# edu_shield.net
KiCad netlist of a schematic drawn in EAGLE
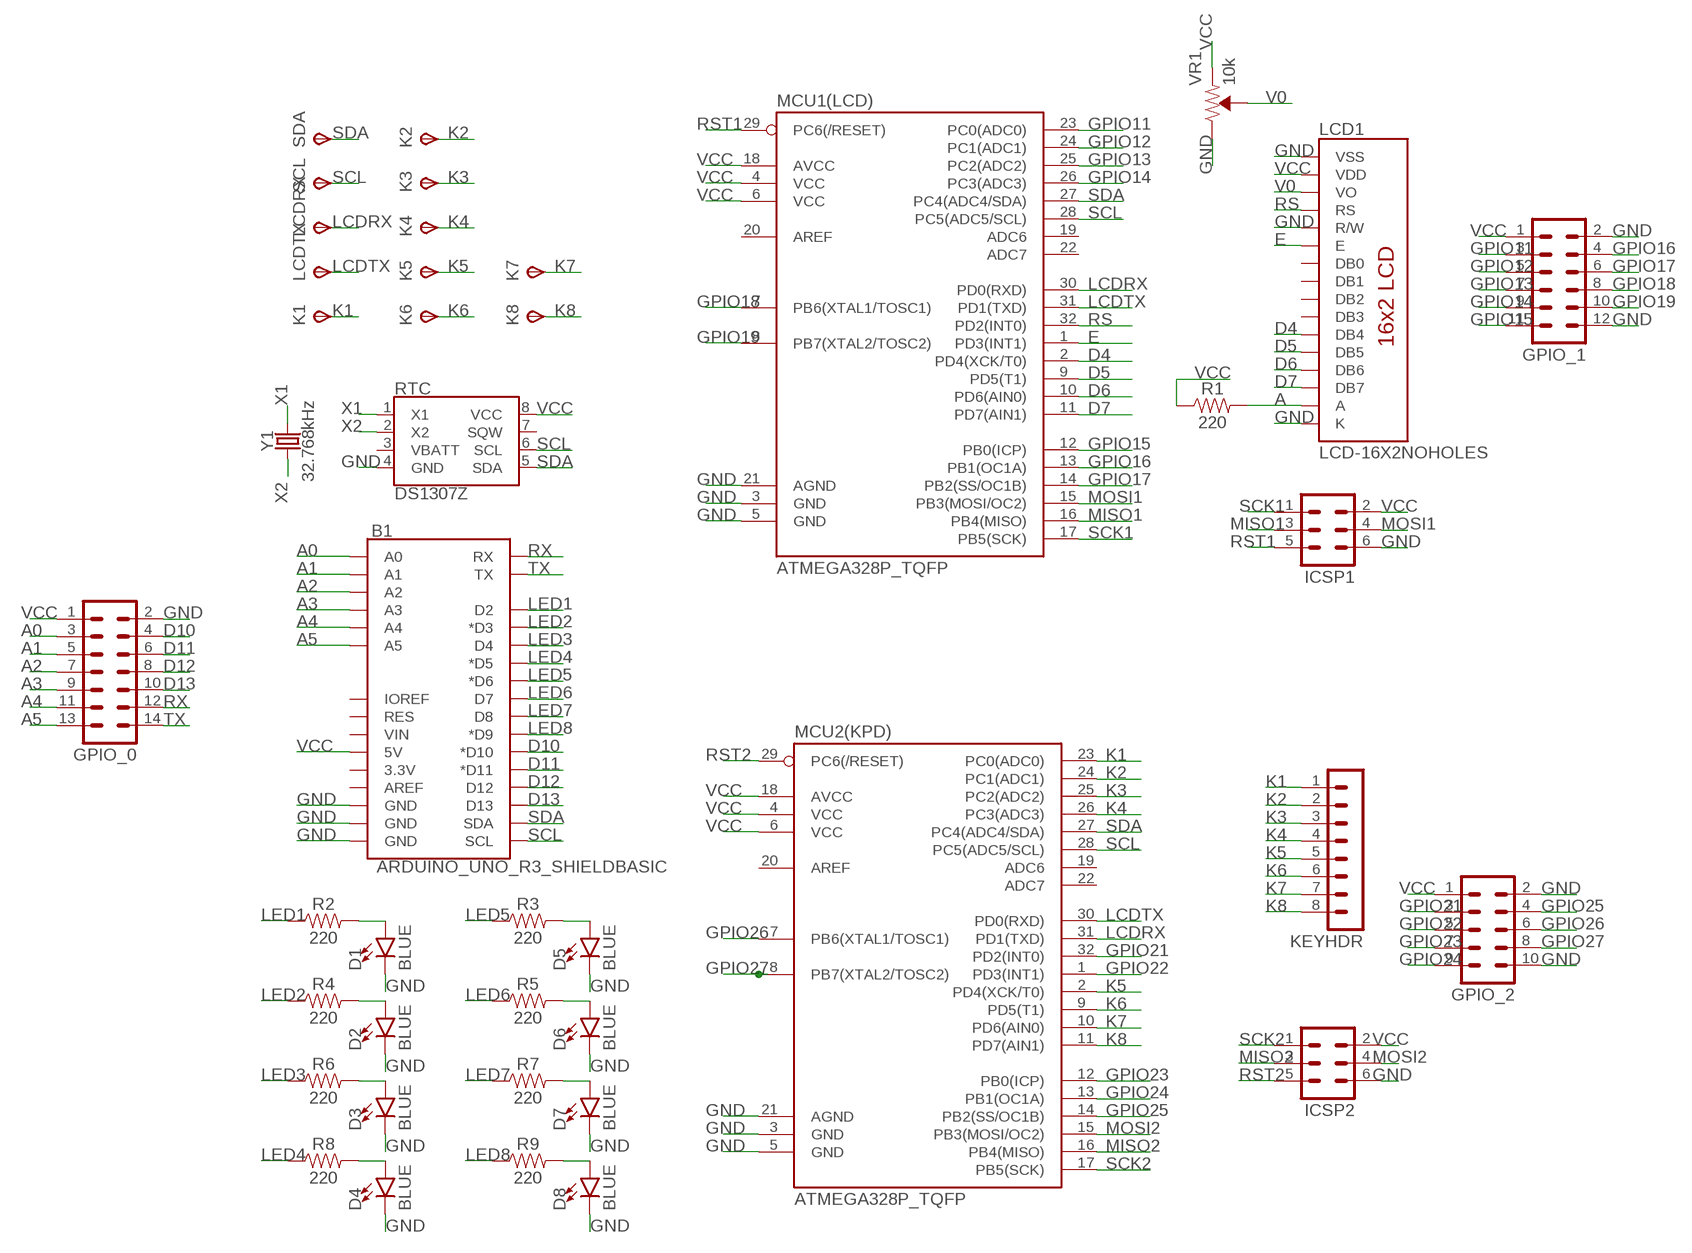
[diagram p0: schematic, sheet 1]

(export (version "E")
  (design (tool "Eeschema 10.0.6"))
  (components
    (comp (ref "B1")
      (value "ARDUINO_UNO_R3_SHIELDBASIC")
      (footprint "eagle-import:UNO_R3_SHIELD")
      (libsource (lib "eagle-import") (part "ARDUINO_UNO_R3_SHIELDBASIC"))
    )
    (comp (ref "D1")
      (value "BLUE")
      (footprint "eagle-import:LED-0603")
      (fields (field (name "MPN") "KPHD-1608LVVBC-D"))
      (libsource (lib "eagle-import") (part "LED-BLUE0603"))
    )
    (comp (ref "D2")
      (value "BLUE")
      (footprint "eagle-import:LED-0603")
      (fields (field (name "MPN") "KPHD-1608LVVBC-D"))
      (libsource (lib "eagle-import") (part "LED-BLUE0603"))
    )
    (comp (ref "D3")
      (value "BLUE")
      (footprint "eagle-import:LED-0603")
      (fields (field (name "MPN") "KPHD-1608LVVBC-D"))
      (libsource (lib "eagle-import") (part "LED-BLUE0603"))
    )
    (comp (ref "D4")
      (value "BLUE")
      (footprint "eagle-import:LED-0603")
      (fields (field (name "MPN") "KPHD-1608LVVBC-D"))
      (libsource (lib "eagle-import") (part "LED-BLUE0603"))
    )
    (comp (ref "D5")
      (value "BLUE")
      (footprint "eagle-import:LED-0603")
      (fields (field (name "MPN") "KPHD-1608LVVBC-D"))
      (libsource (lib "eagle-import") (part "LED-BLUE0603"))
    )
    (comp (ref "D6")
      (value "BLUE")
      (footprint "eagle-import:LED-0603")
      (fields (field (name "MPN") "KPHD-1608LVVBC-D"))
      (libsource (lib "eagle-import") (part "LED-BLUE0603"))
    )
    (comp (ref "D7")
      (value "BLUE")
      (footprint "eagle-import:LED-0603")
      (fields (field (name "MPN") "KPHD-1608LVVBC-D"))
      (libsource (lib "eagle-import") (part "LED-BLUE0603"))
    )
    (comp (ref "D8")
      (value "BLUE")
      (footprint "eagle-import:LED-0603")
      (fields (field (name "MPN") "KPHD-1608LVVBC-D"))
      (libsource (lib "eagle-import") (part "LED-BLUE0603"))
    )
    (comp (ref "GPIO_0")
      (value "MA07-2")
      (footprint "eagle-import:MA07-2")
      (libsource (lib "eagle-import") (part "MA07-2"))
    )
    (comp (ref "GPIO_1")
      (value "MA06-2")
      (footprint "eagle-import:MA06-2")
      (libsource (lib "eagle-import") (part "MA06-2"))
    )
    (comp (ref "GPIO_2")
      (value "MA05-2")
      (footprint "eagle-import:MA05-2")
      (libsource (lib "eagle-import") (part "MA05-2"))
    )
    (comp (ref "ICSP1")
      (value "MA03-2")
      (footprint "eagle-import:MA03-2")
      (libsource (lib "eagle-import") (part "MA03-2"))
    )
    (comp (ref "ICSP2")
      (value "MA03-2")
      (footprint "eagle-import:MA03-2")
      (libsource (lib "eagle-import") (part "MA03-2"))
    )
    (comp (ref "K1")
      (value "TPSTP06SQ")
      (footprint "eagle-import:TP06SQ")
      (libsource (lib "eagle-import") (part "TPSTP06SQ"))
    )
    (comp (ref "K2")
      (value "TPSTP06SQ")
      (footprint "eagle-import:TP06SQ")
      (libsource (lib "eagle-import") (part "TPSTP06SQ"))
    )
    (comp (ref "K3")
      (value "TPSTP06SQ")
      (footprint "eagle-import:TP06SQ")
      (libsource (lib "eagle-import") (part "TPSTP06SQ"))
    )
    (comp (ref "K4")
      (value "TPSTP06SQ")
      (footprint "eagle-import:TP06SQ")
      (libsource (lib "eagle-import") (part "TPSTP06SQ"))
    )
    (comp (ref "K5")
      (value "TPSTP06SQ")
      (footprint "eagle-import:TP06SQ")
      (libsource (lib "eagle-import") (part "TPSTP06SQ"))
    )
    (comp (ref "K6")
      (value "TPSTP06SQ")
      (footprint "eagle-import:TP06SQ")
      (libsource (lib "eagle-import") (part "TPSTP06SQ"))
    )
    (comp (ref "K7")
      (value "TPSTP06SQ")
      (footprint "eagle-import:TP06SQ")
      (libsource (lib "eagle-import") (part "TPSTP06SQ"))
    )
    (comp (ref "K8")
      (value "TPSTP06SQ")
      (footprint "eagle-import:TP06SQ")
      (libsource (lib "eagle-import") (part "TPSTP06SQ"))
    )
    (comp (ref "KEYHDR")
      (value "MA08-1")
      (footprint "eagle-import:MA08-1")
      (libsource (lib "eagle-import") (part "MA08-1"))
    )
    (comp (ref "LCD1")
      (value "LCD-16X2NOHOLES")
      (footprint "eagle-import:LCD-16X2_NOHOLESNOSILK")
      (libsource (lib "eagle-import") (part "LCD-16X2NOHOLES"))
    )
    (comp (ref "LCDRX")
      (value "TPSTP06SQ")
      (footprint "eagle-import:TP06SQ")
      (libsource (lib "eagle-import") (part "TPSTP06SQ"))
    )
    (comp (ref "LCDTX")
      (value "TPSTP06SQ")
      (footprint "eagle-import:TP06SQ")
      (libsource (lib "eagle-import") (part "TPSTP06SQ"))
    )
    (comp (ref "MCU1(LCD)")
      (value "ATMEGA328P_TQFP")
      (footprint "eagle-import:TQFP32-08")
      (libsource (lib "eagle-import") (part "ATMEGA328P_TQFP"))
    )
    (comp (ref "MCU2(KPD)")
      (value "ATMEGA328P_TQFP")
      (footprint "eagle-import:TQFP32-08")
      (libsource (lib "eagle-import") (part "ATMEGA328P_TQFP"))
    )
    (comp (ref "R1")
      (value "220")
      (footprint "eagle-import:0603")
      (fields (field (name "MPN") "MC0603SAF2200T5E"))
      (libsource (lib "eagle-import") (part "220KOHM-0603-1/10W-1%"))
    )
    (comp (ref "R2")
      (value "220")
      (footprint "eagle-import:0603")
      (fields (field (name "MPN") "MC0603SAF2200T5E"))
      (libsource (lib "eagle-import") (part "220KOHM-0603-1/10W-1%"))
    )
    (comp (ref "R3")
      (value "220")
      (footprint "eagle-import:0603")
      (fields (field (name "MPN") "MC0603SAF2200T5E"))
      (libsource (lib "eagle-import") (part "220KOHM-0603-1/10W-1%"))
    )
    (comp (ref "R4")
      (value "220")
      (footprint "eagle-import:0603")
      (fields (field (name "MPN") "MC0603SAF2200T5E"))
      (libsource (lib "eagle-import") (part "220KOHM-0603-1/10W-1%"))
    )
    (comp (ref "R5")
      (value "220")
      (footprint "eagle-import:0603")
      (fields (field (name "MPN") "MC0603SAF2200T5E"))
      (libsource (lib "eagle-import") (part "220KOHM-0603-1/10W-1%"))
    )
    (comp (ref "R6")
      (value "220")
      (footprint "eagle-import:0603")
      (fields (field (name "MPN") "MC0603SAF2200T5E"))
      (libsource (lib "eagle-import") (part "220KOHM-0603-1/10W-1%"))
    )
    (comp (ref "R7")
      (value "220")
      (footprint "eagle-import:0603")
      (fields (field (name "MPN") "MC0603SAF2200T5E"))
      (libsource (lib "eagle-import") (part "220KOHM-0603-1/10W-1%"))
    )
    (comp (ref "R8")
      (value "220")
      (footprint "eagle-import:0603")
      (fields (field (name "MPN") "MC0603SAF2200T5E"))
      (libsource (lib "eagle-import") (part "220KOHM-0603-1/10W-1%"))
    )
    (comp (ref "R9")
      (value "220")
      (footprint "eagle-import:0603")
      (fields (field (name "MPN") "MC0603SAF2200T5E"))
      (libsource (lib "eagle-import") (part "220KOHM-0603-1/10W-1%"))
    )
    (comp (ref "RTC")
      (value "DS1307Z")
      (footprint "eagle-import:SO08-0.15")
      (fields (field (name "MPN") "DS1307Z+T&R"))
      (libsource (lib "eagle-import") (part "DS1307Z"))
    )
    (comp (ref "SCL")
      (value "TPSTP06SQ")
      (footprint "eagle-import:TP06SQ")
      (libsource (lib "eagle-import") (part "TPSTP06SQ"))
    )
    (comp (ref "SDA")
      (value "TPSTP06SQ")
      (footprint "eagle-import:TP06SQ")
      (libsource (lib "eagle-import") (part "TPSTP06SQ"))
    )
    (comp (ref "VR1")
      (value "10k")
      (footprint "eagle-import:TRIMPOT-PTH-3386U")
      (fields (field (name "MF") "BOURNS, INC.") (field (name "MPN") "3296W-1-103LF"))
      (libsource (lib "eagle-import") (part "TRIMPOT-PTH-10MM-KNOB-1/2W-10%"))
    )
    (comp (ref "Y1")
      (value "32.768kHz")
      (footprint "eagle-import:CRYSTAL-PTH-2X6-CYL")
      (fields (field (name "MF") "Abracon Corporation") (field (name "MPN") "AB38T-32.768KHZ"))
      (libsource (lib "eagle-import") (part "CRYSTAL-32.768KHZPTH-2X6"))
    )
  )
  (nets
    (net (code "1") (name "/A") (class "Default")
      (node (ref "LCD1") (pin "15") (pinfunction "A_15") (pintype "power_in"))
      (node (ref "R1") (pin "2") (pinfunction "2_2") (pintype "passive"))
    )
    (net (code "2") (name "/A0") (class "Default")
      (node (ref "B1") (pin "A0") (pinfunction "A0_A0") (pintype "bidirectional"))
      (node (ref "GPIO_0") (pin "3") (pinfunction "3_3") (pintype "passive"))
    )
    (net (code "3") (name "/A1") (class "Default")
      (node (ref "B1") (pin "A1") (pinfunction "A1_A1") (pintype "bidirectional"))
      (node (ref "GPIO_0") (pin "5") (pinfunction "5_5") (pintype "passive"))
    )
    (net (code "4") (name "/A2") (class "Default")
      (node (ref "B1") (pin "A2") (pinfunction "A2_A2") (pintype "bidirectional"))
      (node (ref "GPIO_0") (pin "7") (pinfunction "7_7") (pintype "passive"))
    )
    (net (code "5") (name "/A3") (class "Default")
      (node (ref "B1") (pin "A3") (pinfunction "A3_A3") (pintype "bidirectional"))
      (node (ref "GPIO_0") (pin "9") (pinfunction "9_9") (pintype "passive"))
    )
    (net (code "6") (name "/A4") (class "Default")
      (node (ref "B1") (pin "A4") (pinfunction "A4_A4") (pintype "bidirectional"))
      (node (ref "GPIO_0") (pin "11") (pinfunction "11_11") (pintype "passive"))
    )
    (net (code "7") (name "/A5") (class "Default")
      (node (ref "B1") (pin "A5") (pinfunction "A5_A5") (pintype "bidirectional"))
      (node (ref "GPIO_0") (pin "13") (pinfunction "13_13") (pintype "passive"))
    )
    (net (code "8") (name "/D4") (class "Default")
      (node (ref "LCD1") (pin "11") (pinfunction "DB4_11") (pintype "bidirectional"))
      (node (ref "MCU1(LCD)") (pin "2") (pinfunction "PD4(XCK/T0)_2") (pintype "bidirectional"))
    )
    (net (code "9") (name "/D5") (class "Default")
      (node (ref "LCD1") (pin "12") (pinfunction "DB5_12") (pintype "bidirectional"))
      (node (ref "MCU1(LCD)") (pin "9") (pinfunction "PD5(T1)_9") (pintype "bidirectional"))
    )
    (net (code "10") (name "/D6") (class "Default")
      (node (ref "LCD1") (pin "13") (pinfunction "DB6_13") (pintype "bidirectional"))
      (node (ref "MCU1(LCD)") (pin "10") (pinfunction "PD6(AIN0)_10") (pintype "bidirectional"))
    )
    (net (code "11") (name "/D7") (class "Default")
      (node (ref "LCD1") (pin "14") (pinfunction "DB7_14") (pintype "bidirectional"))
      (node (ref "MCU1(LCD)") (pin "11") (pinfunction "PD7(AIN1)_11") (pintype "bidirectional"))
    )
    (net (code "12") (name "/D10") (class "Default")
      (node (ref "B1") (pin "D10") (pinfunction "*D10_D10") (pintype "bidirectional"))
      (node (ref "GPIO_0") (pin "4") (pinfunction "4_4") (pintype "passive"))
    )
    (net (code "13") (name "/D11") (class "Default")
      (node (ref "B1") (pin "D11") (pinfunction "*D11_D11") (pintype "bidirectional"))
      (node (ref "GPIO_0") (pin "6") (pinfunction "6_6") (pintype "passive"))
    )
    (net (code "14") (name "/D12") (class "Default")
      (node (ref "B1") (pin "D12") (pinfunction "D12_D12") (pintype "bidirectional"))
      (node (ref "GPIO_0") (pin "8") (pinfunction "8_8") (pintype "passive"))
    )
    (net (code "15") (name "/D13") (class "Default")
      (node (ref "B1") (pin "D13") (pinfunction "D13_D13") (pintype "bidirectional"))
      (node (ref "GPIO_0") (pin "10") (pinfunction "10_10") (pintype "passive"))
    )
    (net (code "16") (name "/E") (class "Default")
      (node (ref "LCD1") (pin "6") (pinfunction "E_6") (pintype "input"))
      (node (ref "MCU1(LCD)") (pin "1") (pinfunction "PD3(INT1)_1") (pintype "bidirectional"))
    )
    (net (code "17") (name "/GND") (class "Default")
      (node (ref "B1") (pin "GND@0") (pinfunction "GND_GND@0") (pintype "bidirectional"))
      (node (ref "B1") (pin "GND@1") (pinfunction "GND_GND@1") (pintype "bidirectional"))
      (node (ref "B1") (pin "GND@2") (pinfunction "GND_GND@2") (pintype "bidirectional"))
      (node (ref "D1") (pin "C") (pinfunction "C_C") (pintype "passive"))
      (node (ref "D2") (pin "C") (pinfunction "C_C") (pintype "passive"))
      (node (ref "D3") (pin "C") (pinfunction "C_C") (pintype "passive"))
      (node (ref "D4") (pin "C") (pinfunction "C_C") (pintype "passive"))
      (node (ref "D5") (pin "C") (pinfunction "C_C") (pintype "passive"))
      (node (ref "D6") (pin "C") (pinfunction "C_C") (pintype "passive"))
      (node (ref "D7") (pin "C") (pinfunction "C_C") (pintype "passive"))
      (node (ref "D8") (pin "C") (pinfunction "C_C") (pintype "passive"))
      (node (ref "GPIO_0") (pin "2") (pinfunction "2_2") (pintype "passive"))
      (node (ref "GPIO_1") (pin "12") (pinfunction "12_12") (pintype "passive"))
      (node (ref "GPIO_1") (pin "2") (pinfunction "2_2") (pintype "passive"))
      (node (ref "GPIO_2") (pin "10") (pinfunction "10_10") (pintype "passive"))
      (node (ref "GPIO_2") (pin "2") (pinfunction "2_2") (pintype "passive"))
      (node (ref "ICSP1") (pin "6") (pinfunction "6_6") (pintype "passive"))
      (node (ref "ICSP2") (pin "6") (pinfunction "6_6") (pintype "passive"))
      (node (ref "LCD1") (pin "1") (pinfunction "VSS_1") (pintype "power_in"))
      (node (ref "LCD1") (pin "16") (pinfunction "K_16") (pintype "power_in"))
      (node (ref "LCD1") (pin "5") (pinfunction "R/W_5") (pintype "input"))
      (node (ref "MCU1(LCD)") (pin "21") (pinfunction "AGND_21") (pintype "bidirectional"))
      (node (ref "MCU1(LCD)") (pin "3") (pinfunction "GND_3") (pintype "bidirectional"))
      (node (ref "MCU1(LCD)") (pin "5") (pinfunction "GND_5") (pintype "bidirectional"))
      (node (ref "MCU2(KPD)") (pin "21") (pinfunction "AGND_21") (pintype "bidirectional"))
      (node (ref "MCU2(KPD)") (pin "3") (pinfunction "GND_3") (pintype "bidirectional"))
      (node (ref "MCU2(KPD)") (pin "5") (pinfunction "GND_5") (pintype "bidirectional"))
      (node (ref "RTC") (pin "4") (pinfunction "GND_4") (pintype "bidirectional"))
      (node (ref "VR1") (pin "3") (pinfunction "CW_3") (pintype "passive"))
    )
    (net (code "18") (name "/GPIO11") (class "Default")
      (node (ref "GPIO_1") (pin "3") (pinfunction "3_3") (pintype "passive"))
      (node (ref "MCU1(LCD)") (pin "23") (pinfunction "PC0(ADC0)_23") (pintype "bidirectional"))
    )
    (net (code "19") (name "/GPIO12") (class "Default")
      (node (ref "GPIO_1") (pin "5") (pinfunction "5_5") (pintype "passive"))
      (node (ref "MCU1(LCD)") (pin "24") (pinfunction "PC1(ADC1)_24") (pintype "bidirectional"))
    )
    (net (code "20") (name "/GPIO13") (class "Default")
      (node (ref "GPIO_1") (pin "7") (pinfunction "7_7") (pintype "passive"))
      (node (ref "MCU1(LCD)") (pin "25") (pinfunction "PC2(ADC2)_25") (pintype "bidirectional"))
    )
    (net (code "21") (name "/GPIO14") (class "Default")
      (node (ref "GPIO_1") (pin "9") (pinfunction "9_9") (pintype "passive"))
      (node (ref "MCU1(LCD)") (pin "26") (pinfunction "PC3(ADC3)_26") (pintype "bidirectional"))
    )
    (net (code "22") (name "/GPIO15") (class "Default")
      (node (ref "GPIO_1") (pin "11") (pinfunction "11_11") (pintype "passive"))
      (node (ref "MCU1(LCD)") (pin "12") (pinfunction "PB0(ICP)_12") (pintype "bidirectional"))
    )
    (net (code "23") (name "/GPIO16") (class "Default")
      (node (ref "GPIO_1") (pin "4") (pinfunction "4_4") (pintype "passive"))
      (node (ref "MCU1(LCD)") (pin "13") (pinfunction "PB1(OC1A)_13") (pintype "bidirectional"))
    )
    (net (code "24") (name "/GPIO17") (class "Default")
      (node (ref "GPIO_1") (pin "6") (pinfunction "6_6") (pintype "passive"))
      (node (ref "MCU1(LCD)") (pin "14") (pinfunction "PB2(SS/OC1B)_14") (pintype "bidirectional"))
    )
    (net (code "25") (name "/GPIO18") (class "Default")
      (node (ref "GPIO_1") (pin "8") (pinfunction "8_8") (pintype "passive"))
      (node (ref "MCU1(LCD)") (pin "7") (pinfunction "PB6(XTAL1/TOSC1)_7") (pintype "bidirectional"))
    )
    (net (code "26") (name "/GPIO19") (class "Default")
      (node (ref "GPIO_1") (pin "10") (pinfunction "10_10") (pintype "passive"))
      (node (ref "MCU1(LCD)") (pin "8") (pinfunction "PB7(XTAL2/TOSC2)_8") (pintype "bidirectional"))
    )
    (net (code "27") (name "/GPIO21") (class "Default")
      (node (ref "GPIO_2") (pin "3") (pinfunction "3_3") (pintype "passive"))
      (node (ref "MCU2(KPD)") (pin "32") (pinfunction "PD2(INT0)_32") (pintype "bidirectional"))
    )
    (net (code "28") (name "/GPIO22") (class "Default")
      (node (ref "GPIO_2") (pin "5") (pinfunction "5_5") (pintype "passive"))
      (node (ref "MCU2(KPD)") (pin "1") (pinfunction "PD3(INT1)_1") (pintype "bidirectional"))
    )
    (net (code "29") (name "/GPIO23") (class "Default")
      (node (ref "GPIO_2") (pin "7") (pinfunction "7_7") (pintype "passive"))
      (node (ref "MCU2(KPD)") (pin "12") (pinfunction "PB0(ICP)_12") (pintype "bidirectional"))
    )
    (net (code "30") (name "/GPIO24") (class "Default")
      (node (ref "GPIO_2") (pin "9") (pinfunction "9_9") (pintype "passive"))
      (node (ref "MCU2(KPD)") (pin "13") (pinfunction "PB1(OC1A)_13") (pintype "bidirectional"))
    )
    (net (code "31") (name "/GPIO25") (class "Default")
      (node (ref "GPIO_2") (pin "4") (pinfunction "4_4") (pintype "passive"))
      (node (ref "MCU2(KPD)") (pin "14") (pinfunction "PB2(SS/OC1B)_14") (pintype "bidirectional"))
    )
    (net (code "32") (name "/GPIO26") (class "Default")
      (node (ref "GPIO_2") (pin "6") (pinfunction "6_6") (pintype "passive"))
      (node (ref "MCU2(KPD)") (pin "7") (pinfunction "PB6(XTAL1/TOSC1)_7") (pintype "bidirectional"))
    )
    (net (code "33") (name "/GPIO27") (class "Default")
      (node (ref "GPIO_2") (pin "8") (pinfunction "8_8") (pintype "passive"))
      (node (ref "MCU2(KPD)") (pin "8") (pinfunction "PB7(XTAL2/TOSC2)_8") (pintype "bidirectional"))
    )
    (net (code "34") (name "/K1") (class "Default")
      (node (ref "K1") (pin "TP") (pinfunction "PP_TP") (pintype "input"))
      (node (ref "KEYHDR") (pin "1") (pinfunction "1_1") (pintype "passive"))
      (node (ref "MCU2(KPD)") (pin "23") (pinfunction "PC0(ADC0)_23") (pintype "bidirectional"))
    )
    (net (code "35") (name "/K2") (class "Default")
      (node (ref "K2") (pin "TP") (pinfunction "PP_TP") (pintype "input"))
      (node (ref "KEYHDR") (pin "2") (pinfunction "2_2") (pintype "passive"))
      (node (ref "MCU2(KPD)") (pin "24") (pinfunction "PC1(ADC1)_24") (pintype "bidirectional"))
    )
    (net (code "36") (name "/K3") (class "Default")
      (node (ref "K3") (pin "TP") (pinfunction "PP_TP") (pintype "input"))
      (node (ref "KEYHDR") (pin "3") (pinfunction "3_3") (pintype "passive"))
      (node (ref "MCU2(KPD)") (pin "25") (pinfunction "PC2(ADC2)_25") (pintype "bidirectional"))
    )
    (net (code "37") (name "/K4") (class "Default")
      (node (ref "K4") (pin "TP") (pinfunction "PP_TP") (pintype "input"))
      (node (ref "KEYHDR") (pin "4") (pinfunction "4_4") (pintype "passive"))
      (node (ref "MCU2(KPD)") (pin "26") (pinfunction "PC3(ADC3)_26") (pintype "bidirectional"))
    )
    (net (code "38") (name "/K5") (class "Default")
      (node (ref "K5") (pin "TP") (pinfunction "PP_TP") (pintype "input"))
      (node (ref "KEYHDR") (pin "5") (pinfunction "5_5") (pintype "passive"))
      (node (ref "MCU2(KPD)") (pin "2") (pinfunction "PD4(XCK/T0)_2") (pintype "bidirectional"))
    )
    (net (code "39") (name "/K6") (class "Default")
      (node (ref "K6") (pin "TP") (pinfunction "PP_TP") (pintype "input"))
      (node (ref "KEYHDR") (pin "6") (pinfunction "6_6") (pintype "passive"))
      (node (ref "MCU2(KPD)") (pin "9") (pinfunction "PD5(T1)_9") (pintype "bidirectional"))
    )
    (net (code "40") (name "/K7") (class "Default")
      (node (ref "K7") (pin "TP") (pinfunction "PP_TP") (pintype "input"))
      (node (ref "KEYHDR") (pin "7") (pinfunction "7_7") (pintype "passive"))
      (node (ref "MCU2(KPD)") (pin "10") (pinfunction "PD6(AIN0)_10") (pintype "bidirectional"))
    )
    (net (code "41") (name "/K8") (class "Default")
      (node (ref "K8") (pin "TP") (pinfunction "PP_TP") (pintype "input"))
      (node (ref "KEYHDR") (pin "8") (pinfunction "8_8") (pintype "passive"))
      (node (ref "MCU2(KPD)") (pin "11") (pinfunction "PD7(AIN1)_11") (pintype "bidirectional"))
    )
    (net (code "42") (name "/LCDRX") (class "Default")
      (node (ref "LCDRX") (pin "TP") (pinfunction "PP_TP") (pintype "input"))
      (node (ref "MCU1(LCD)") (pin "30") (pinfunction "PD0(RXD)_30") (pintype "bidirectional"))
      (node (ref "MCU2(KPD)") (pin "31") (pinfunction "PD1(TXD)_31") (pintype "bidirectional"))
    )
    (net (code "43") (name "/LCDTX") (class "Default")
      (node (ref "LCDTX") (pin "TP") (pinfunction "PP_TP") (pintype "input"))
      (node (ref "MCU1(LCD)") (pin "31") (pinfunction "PD1(TXD)_31") (pintype "bidirectional"))
      (node (ref "MCU2(KPD)") (pin "30") (pinfunction "PD0(RXD)_30") (pintype "bidirectional"))
    )
    (net (code "44") (name "/LED1") (class "Default")
      (node (ref "B1") (pin "D2") (pinfunction "D2_D2") (pintype "bidirectional"))
      (node (ref "R2") (pin "1") (pinfunction "1_1") (pintype "passive"))
    )
    (net (code "45") (name "/LED2") (class "Default")
      (node (ref "B1") (pin "D3") (pinfunction "*D3_D3") (pintype "bidirectional"))
      (node (ref "R4") (pin "1") (pinfunction "1_1") (pintype "passive"))
    )
    (net (code "46") (name "/LED3") (class "Default")
      (node (ref "B1") (pin "D4") (pinfunction "D4_D4") (pintype "bidirectional"))
      (node (ref "R6") (pin "1") (pinfunction "1_1") (pintype "passive"))
    )
    (net (code "47") (name "/LED4") (class "Default")
      (node (ref "B1") (pin "D5") (pinfunction "*D5_D5") (pintype "bidirectional"))
      (node (ref "R8") (pin "1") (pinfunction "1_1") (pintype "passive"))
    )
    (net (code "48") (name "/LED5") (class "Default")
      (node (ref "B1") (pin "D6") (pinfunction "*D6_D6") (pintype "bidirectional"))
      (node (ref "R3") (pin "1") (pinfunction "1_1") (pintype "passive"))
    )
    (net (code "49") (name "/LED6") (class "Default")
      (node (ref "B1") (pin "D7") (pinfunction "D7_D7") (pintype "bidirectional"))
      (node (ref "R5") (pin "1") (pinfunction "1_1") (pintype "passive"))
    )
    (net (code "50") (name "/LED7") (class "Default")
      (node (ref "B1") (pin "D8") (pinfunction "D8_D8") (pintype "bidirectional"))
      (node (ref "R7") (pin "1") (pinfunction "1_1") (pintype "passive"))
    )
    (net (code "51") (name "/LED8") (class "Default")
      (node (ref "B1") (pin "D9") (pinfunction "*D9_D9") (pintype "bidirectional"))
      (node (ref "R9") (pin "1") (pinfunction "1_1") (pintype "passive"))
    )
    (net (code "52") (name "/MISO1") (class "Default")
      (node (ref "ICSP1") (pin "3") (pinfunction "3_3") (pintype "passive"))
      (node (ref "MCU1(LCD)") (pin "16") (pinfunction "PB4(MISO)_16") (pintype "bidirectional"))
    )
    (net (code "53") (name "/MISO2") (class "Default")
      (node (ref "ICSP2") (pin "3") (pinfunction "3_3") (pintype "passive"))
      (node (ref "MCU2(KPD)") (pin "16") (pinfunction "PB4(MISO)_16") (pintype "bidirectional"))
    )
    (net (code "54") (name "/MOSI1") (class "Default")
      (node (ref "ICSP1") (pin "4") (pinfunction "4_4") (pintype "passive"))
      (node (ref "MCU1(LCD)") (pin "15") (pinfunction "PB3(MOSI/OC2)_15") (pintype "bidirectional"))
    )
    (net (code "55") (name "/MOSI2") (class "Default")
      (node (ref "ICSP2") (pin "4") (pinfunction "4_4") (pintype "passive"))
      (node (ref "MCU2(KPD)") (pin "15") (pinfunction "PB3(MOSI/OC2)_15") (pintype "bidirectional"))
    )
    (net (code "56") (name "/RS") (class "Default")
      (node (ref "LCD1") (pin "4") (pinfunction "RS_4") (pintype "input"))
      (node (ref "MCU1(LCD)") (pin "32") (pinfunction "PD2(INT0)_32") (pintype "bidirectional"))
    )
    (net (code "57") (name "/RST1") (class "Default")
      (node (ref "ICSP1") (pin "5") (pinfunction "5_5") (pintype "passive"))
      (node (ref "MCU1(LCD)") (pin "29") (pinfunction "PC6(/RESET)_29") (pintype "bidirectional"))
    )
    (net (code "58") (name "/RST2") (class "Default")
      (node (ref "ICSP2") (pin "5") (pinfunction "5_5") (pintype "passive"))
      (node (ref "MCU2(KPD)") (pin "29") (pinfunction "PC6(/RESET)_29") (pintype "bidirectional"))
    )
    (net (code "59") (name "/RX") (class "Default")
      (node (ref "B1") (pin "RX") (pinfunction "RX_RX") (pintype "bidirectional"))
      (node (ref "GPIO_0") (pin "12") (pinfunction "12_12") (pintype "passive"))
    )
    (net (code "60") (name "/SCK1") (class "Default")
      (node (ref "ICSP1") (pin "1") (pinfunction "1_1") (pintype "passive"))
      (node (ref "MCU1(LCD)") (pin "17") (pinfunction "PB5(SCK)_17") (pintype "bidirectional"))
    )
    (net (code "61") (name "/SCK2") (class "Default")
      (node (ref "ICSP2") (pin "1") (pinfunction "1_1") (pintype "passive"))
      (node (ref "MCU2(KPD)") (pin "17") (pinfunction "PB5(SCK)_17") (pintype "bidirectional"))
    )
    (net (code "62") (name "/SCL") (class "Default")
      (node (ref "B1") (pin "SCL") (pinfunction "SCL_SCL") (pintype "bidirectional"))
      (node (ref "MCU1(LCD)") (pin "28") (pinfunction "PC5(ADC5/SCL)_28") (pintype "bidirectional"))
      (node (ref "MCU2(KPD)") (pin "28") (pinfunction "PC5(ADC5/SCL)_28") (pintype "bidirectional"))
      (node (ref "RTC") (pin "6") (pinfunction "SCL_6") (pintype "bidirectional"))
      (node (ref "SCL") (pin "TP") (pinfunction "PP_TP") (pintype "input"))
    )
    (net (code "63") (name "/SDA") (class "Default")
      (node (ref "B1") (pin "SDA") (pinfunction "SDA_SDA") (pintype "bidirectional"))
      (node (ref "MCU1(LCD)") (pin "27") (pinfunction "PC4(ADC4/SDA)_27") (pintype "bidirectional"))
      (node (ref "MCU2(KPD)") (pin "27") (pinfunction "PC4(ADC4/SDA)_27") (pintype "bidirectional"))
      (node (ref "RTC") (pin "5") (pinfunction "SDA_5") (pintype "bidirectional"))
      (node (ref "SDA") (pin "TP") (pinfunction "PP_TP") (pintype "input"))
    )
    (net (code "64") (name "/TX") (class "Default")
      (node (ref "B1") (pin "TX") (pinfunction "TX_TX") (pintype "bidirectional"))
      (node (ref "GPIO_0") (pin "14") (pinfunction "14_14") (pintype "passive"))
    )
    (net (code "65") (name "/V0") (class "Default")
      (node (ref "LCD1") (pin "3") (pinfunction "VO_3") (pintype "bidirectional"))
      (node (ref "VR1") (pin "2") (pinfunction "WIPER_2") (pintype "passive"))
    )
    (net (code "66") (name "/VCC") (class "Default")
      (node (ref "B1") (pin "5V") (pinfunction "5V_5V") (pintype "bidirectional"))
      (node (ref "GPIO_0") (pin "1") (pinfunction "1_1") (pintype "passive"))
      (node (ref "GPIO_1") (pin "1") (pinfunction "1_1") (pintype "passive"))
      (node (ref "GPIO_2") (pin "1") (pinfunction "1_1") (pintype "passive"))
      (node (ref "ICSP1") (pin "2") (pinfunction "2_2") (pintype "passive"))
      (node (ref "ICSP2") (pin "2") (pinfunction "2_2") (pintype "passive"))
      (node (ref "LCD1") (pin "2") (pinfunction "VDD_2") (pintype "power_in"))
      (node (ref "MCU1(LCD)") (pin "18") (pinfunction "AVCC_18") (pintype "bidirectional"))
      (node (ref "MCU1(LCD)") (pin "4") (pinfunction "VCC_4") (pintype "bidirectional"))
      (node (ref "MCU1(LCD)") (pin "6") (pinfunction "VCC_6") (pintype "bidirectional"))
      (node (ref "MCU2(KPD)") (pin "18") (pinfunction "AVCC_18") (pintype "bidirectional"))
      (node (ref "MCU2(KPD)") (pin "4") (pinfunction "VCC_4") (pintype "bidirectional"))
      (node (ref "MCU2(KPD)") (pin "6") (pinfunction "VCC_6") (pintype "bidirectional"))
      (node (ref "R1") (pin "1") (pinfunction "1_1") (pintype "passive"))
      (node (ref "RTC") (pin "8") (pinfunction "VCC_8") (pintype "bidirectional"))
      (node (ref "VR1") (pin "1") (pinfunction "CCW_1") (pintype "passive"))
    )
    (net (code "67") (name "/X1") (class "Default")
      (node (ref "RTC") (pin "1") (pinfunction "X1_1") (pintype "bidirectional"))
      (node (ref "Y1") (pin "2") (pinfunction "2_2") (pintype "passive"))
    )
    (net (code "68") (name "/X2") (class "Default")
      (node (ref "RTC") (pin "2") (pinfunction "X2_2") (pintype "bidirectional"))
      (node (ref "Y1") (pin "1") (pinfunction "1_1") (pintype "passive"))
    )
    (net (code "69") (name "Net-(D1-PadA)") (class "Default")
      (node (ref "D1") (pin "A") (pinfunction "A_A") (pintype "passive"))
      (node (ref "R2") (pin "2") (pinfunction "2_2") (pintype "passive"))
    )
    (net (code "70") (name "Net-(D2-PadA)") (class "Default")
      (node (ref "D2") (pin "A") (pinfunction "A_A") (pintype "passive"))
      (node (ref "R4") (pin "2") (pinfunction "2_2") (pintype "passive"))
    )
    (net (code "71") (name "Net-(D3-PadA)") (class "Default")
      (node (ref "D3") (pin "A") (pinfunction "A_A") (pintype "passive"))
      (node (ref "R6") (pin "2") (pinfunction "2_2") (pintype "passive"))
    )
    (net (code "72") (name "Net-(D4-PadA)") (class "Default")
      (node (ref "D4") (pin "A") (pinfunction "A_A") (pintype "passive"))
      (node (ref "R8") (pin "2") (pinfunction "2_2") (pintype "passive"))
    )
    (net (code "73") (name "Net-(D5-PadA)") (class "Default")
      (node (ref "D5") (pin "A") (pinfunction "A_A") (pintype "passive"))
      (node (ref "R3") (pin "2") (pinfunction "2_2") (pintype "passive"))
    )
    (net (code "74") (name "Net-(D6-PadA)") (class "Default")
      (node (ref "D6") (pin "A") (pinfunction "A_A") (pintype "passive"))
      (node (ref "R5") (pin "2") (pinfunction "2_2") (pintype "passive"))
    )
    (net (code "75") (name "Net-(D7-PadA)") (class "Default")
      (node (ref "D7") (pin "A") (pinfunction "A_A") (pintype "passive"))
      (node (ref "R7") (pin "2") (pinfunction "2_2") (pintype "passive"))
    )
    (net (code "76") (name "Net-(D8-PadA)") (class "Default")
      (node (ref "D8") (pin "A") (pinfunction "A_A") (pintype "passive"))
      (node (ref "R9") (pin "2") (pinfunction "2_2") (pintype "passive"))
    )
    (net (code "77") (name "unconnected-(B1-Pad3.3V)") (class "Default")
      (node (ref "B1") (pin "3.3V") (pinfunction "3.3V_3.3V") (pintype "bidirectional"))
    )
    (net (code "78") (name "unconnected-(B1-PadAREF)") (class "Default")
      (node (ref "B1") (pin "AREF") (pinfunction "AREF_AREF") (pintype "bidirectional"))
    )
    (net (code "79") (name "unconnected-(B1-PadIOREF)") (class "Default")
      (node (ref "B1") (pin "IOREF") (pinfunction "IOREF_IOREF") (pintype "bidirectional"))
    )
    (net (code "80") (name "unconnected-(B1-PadRES)") (class "Default")
      (node (ref "B1") (pin "RES") (pinfunction "RES_RES") (pintype "bidirectional"))
    )
    (net (code "81") (name "unconnected-(B1-PadVIN)") (class "Default")
      (node (ref "B1") (pin "VIN") (pinfunction "VIN_VIN") (pintype "bidirectional"))
    )
    (net (code "82") (name "unconnected-(LCD1-DB0-Pad7)") (class "Default")
      (node (ref "LCD1") (pin "7") (pinfunction "DB0_7") (pintype "bidirectional"))
    )
    (net (code "83") (name "unconnected-(LCD1-DB1-Pad8)") (class "Default")
      (node (ref "LCD1") (pin "8") (pinfunction "DB1_8") (pintype "bidirectional"))
    )
    (net (code "84") (name "unconnected-(LCD1-DB2-Pad9)") (class "Default")
      (node (ref "LCD1") (pin "9") (pinfunction "DB2_9") (pintype "bidirectional"))
    )
    (net (code "85") (name "unconnected-(LCD1-DB3-Pad10)") (class "Default")
      (node (ref "LCD1") (pin "10") (pinfunction "DB3_10") (pintype "bidirectional"))
    )
    (net (code "86") (name "unconnected-(MCU1(LCD)-ADC6-Pad19)") (class "Default")
      (node (ref "MCU1(LCD)") (pin "19") (pinfunction "ADC6_19") (pintype "bidirectional"))
    )
    (net (code "87") (name "unconnected-(MCU1(LCD)-ADC7-Pad22)") (class "Default")
      (node (ref "MCU1(LCD)") (pin "22") (pinfunction "ADC7_22") (pintype "bidirectional"))
    )
    (net (code "88") (name "unconnected-(MCU1(LCD)-AREF-Pad20)") (class "Default")
      (node (ref "MCU1(LCD)") (pin "20") (pinfunction "AREF_20") (pintype "bidirectional"))
    )
    (net (code "89") (name "unconnected-(MCU2(KPD)-ADC6-Pad19)") (class "Default")
      (node (ref "MCU2(KPD)") (pin "19") (pinfunction "ADC6_19") (pintype "bidirectional"))
    )
    (net (code "90") (name "unconnected-(MCU2(KPD)-ADC7-Pad22)") (class "Default")
      (node (ref "MCU2(KPD)") (pin "22") (pinfunction "ADC7_22") (pintype "bidirectional"))
    )
    (net (code "91") (name "unconnected-(MCU2(KPD)-AREF-Pad20)") (class "Default")
      (node (ref "MCU2(KPD)") (pin "20") (pinfunction "AREF_20") (pintype "bidirectional"))
    )
    (net (code "92") (name "unconnected-(RTC-SQW-Pad7)") (class "Default")
      (node (ref "RTC") (pin "7") (pinfunction "SQW_7") (pintype "bidirectional"))
    )
    (net (code "93") (name "unconnected-(RTC-VBATT-Pad3)") (class "Default")
      (node (ref "RTC") (pin "3") (pinfunction "VBATT_3") (pintype "bidirectional"))
    )
  )
)
